# MCH_FPGA_Banks_66_68_HP_FMC.net
KiCad netlist of a schematic drawn in Altium Designer
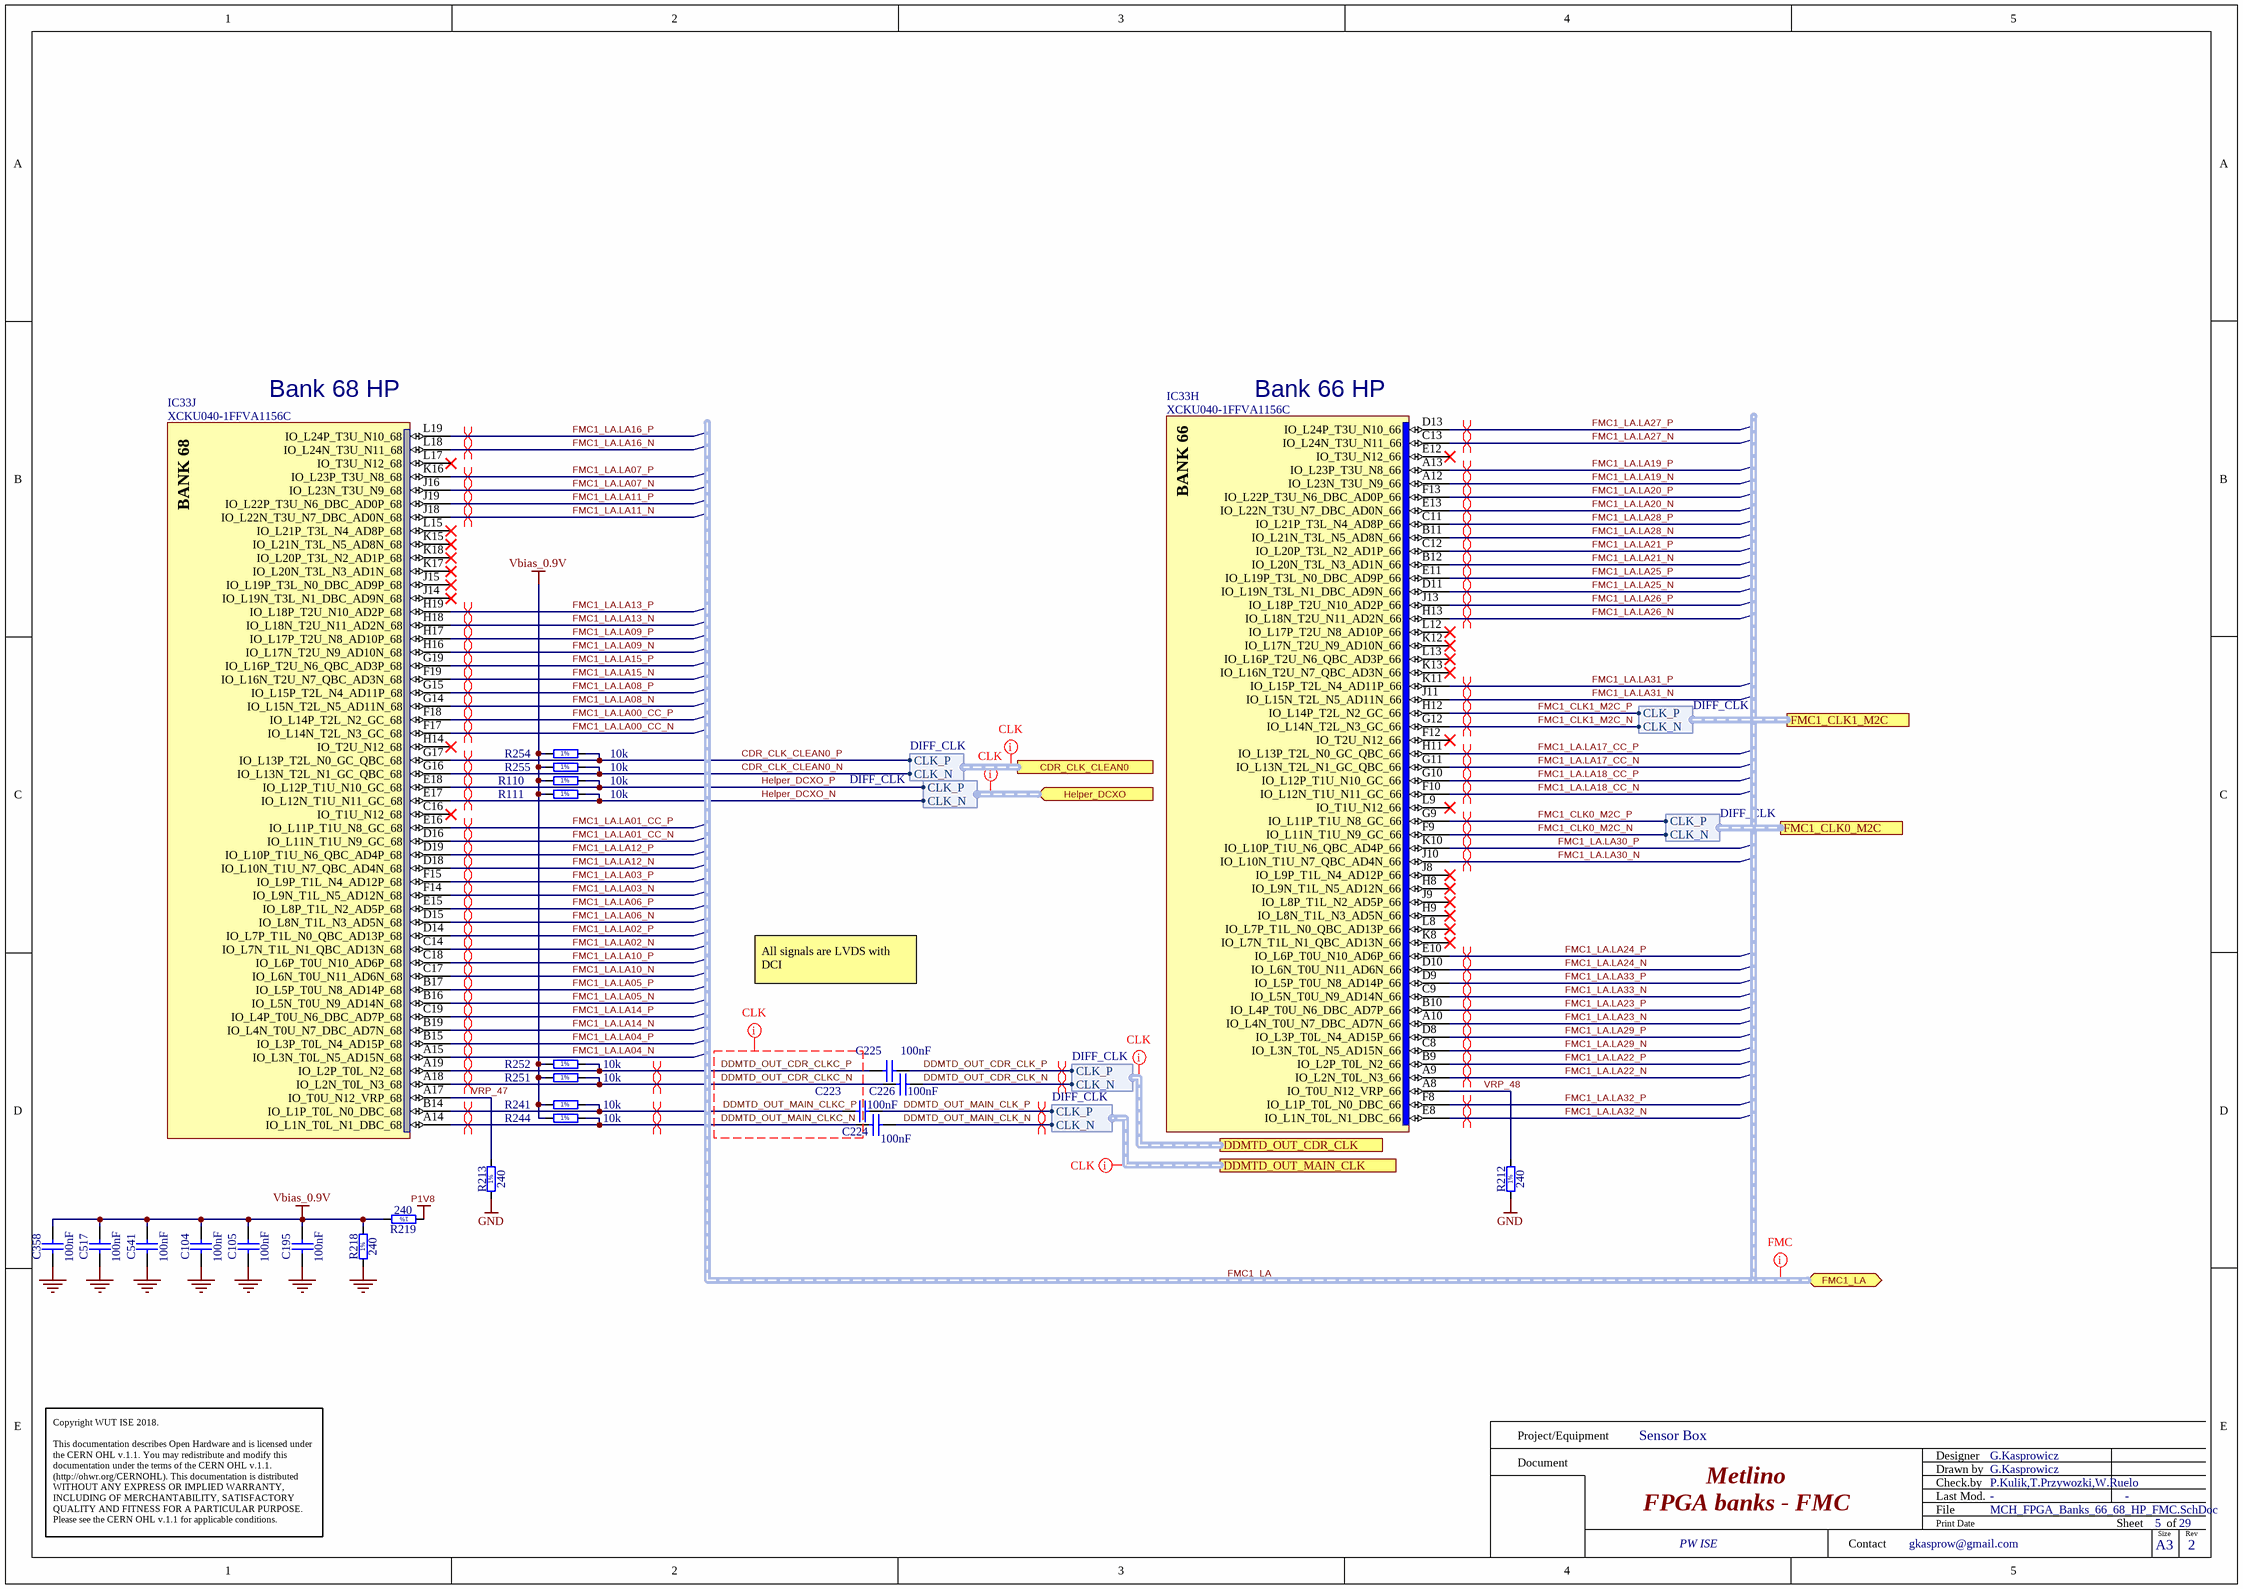
[diagram p0: MCH_FPGA_Banks_66_68_HP_FMC.SchDoc]

(export (version "E")
  (design (tool "Eeschema 10.0.6"))
  (components
    (comp (ref "C104")
      (value "100nF")
      (footprint "CAPC0603X33N")
      (description "Non-polarised capacitor")
      (fields
        (field (name "MANUFACTURER PART NUMBER") "CC0201_100NF_6.3V_10%_X5R")
        (field (name "MANUFACTURER") "GENERIC")
        (field (name "AUTHOR") "CERN DEM JLC")
      )
      (libsource (lib "Capacitors") (part "Capacitor - non polarized"))
    )
    (comp (ref "C105")
      (value "100nF")
      (footprint "CAPC0603X33N")
      (description "Non-polarised capacitor")
      (fields
        (field (name "MANUFACTURER PART NUMBER") "CC0201_100NF_6.3V_10%_X5R")
        (field (name "MANUFACTURER") "GENERIC")
        (field (name "AUTHOR") "CERN DEM JLC")
      )
      (libsource (lib "Capacitors") (part "Capacitor - non polarized"))
    )
    (comp (ref "C195")
      (value "100nF")
      (footprint "CAPC0603X33N")
      (description "Non-polarised capacitor")
      (fields
        (field (name "MANUFACTURER PART NUMBER") "CC0201_100NF_6.3V_10%_X5R")
        (field (name "MANUFACTURER") "GENERIC")
        (field (name "AUTHOR") "CERN DEM JLC")
      )
      (libsource (lib "Capacitors") (part "Capacitor - non polarized"))
    )
    (comp (ref "C223")
      (value "100nF")
      (footprint "CAPC0603X33N")
      (description "Non-polarised capacitor")
      (fields
        (field (name "MANUFACTURER PART NUMBER") "CC0201_100NF_6.3V_10%_X5R")
        (field (name "MANUFACTURER") "GENERIC")
        (field (name "AUTHOR") "CERN DEM JLC")
      )
      (libsource (lib "Capacitors") (part "Capacitor - non polarized"))
    )
    (comp (ref "C224")
      (value "100nF")
      (footprint "CAPC0603X33N")
      (description "Non-polarised capacitor")
      (fields
        (field (name "MANUFACTURER PART NUMBER") "CC0201_100NF_6.3V_10%_X5R")
        (field (name "MANUFACTURER") "GENERIC")
        (field (name "AUTHOR") "CERN DEM JLC")
      )
      (libsource (lib "Capacitors") (part "Capacitor - non polarized"))
    )
    (comp (ref "C225")
      (value "100nF")
      (footprint "CAPC0603X33N")
      (description "Non-polarised capacitor")
      (fields
        (field (name "MANUFACTURER PART NUMBER") "CC0201_100NF_6.3V_10%_X5R")
        (field (name "MANUFACTURER") "GENERIC")
        (field (name "AUTHOR") "CERN DEM JLC")
      )
      (libsource (lib "Capacitors") (part "Capacitor - non polarized"))
    )
    (comp (ref "C226")
      (value "100nF")
      (footprint "CAPC0603X33N")
      (description "Non-polarised capacitor")
      (fields
        (field (name "MANUFACTURER PART NUMBER") "CC0201_100NF_6.3V_10%_X5R")
        (field (name "MANUFACTURER") "GENERIC")
        (field (name "AUTHOR") "CERN DEM JLC")
      )
      (libsource (lib "Capacitors") (part "Capacitor - non polarized"))
    )
    (comp (ref "C358")
      (value "100nF")
      (footprint "CAPC0603X33N")
      (description "Non-polarised capacitor")
      (fields
        (field (name "MANUFACTURER PART NUMBER") "CC0201_100NF_6.3V_10%_X5R")
        (field (name "MANUFACTURER") "GENERIC")
        (field (name "AUTHOR") "CERN DEM JLC")
      )
      (libsource (lib "Capacitors") (part "Capacitor - non polarized"))
    )
    (comp (ref "C517")
      (value "100nF")
      (footprint "CAPC0603X33N")
      (description "Non-polarised capacitor")
      (fields
        (field (name "MANUFACTURER PART NUMBER") "CC0201_100NF_6.3V_10%_X5R")
        (field (name "MANUFACTURER") "GENERIC")
        (field (name "AUTHOR") "CERN DEM JLC")
      )
      (libsource (lib "Capacitors") (part "Capacitor - non polarized"))
    )
    (comp (ref "C541")
      (value "100nF")
      (footprint "CAPC0603X33N")
      (description "Non-polarised capacitor")
      (fields
        (field (name "MANUFACTURER PART NUMBER") "CC0201_100NF_6.3V_10%_X5R")
        (field (name "MANUFACTURER") "GENERIC")
        (field (name "AUTHOR") "CERN DEM JLC")
      )
      (libsource (lib "Capacitors") (part "Capacitor - non polarized"))
    )
    (comp (ref "IC33")
      (value "XCKU040-1FFVA1156C")
      (footprint "BGA1156C100P34X34_3500X3500X350")
      (description "Kintex UltraScale FPGA, 520 I/O, 530K Cells, 1156-Ball BGA, Speed Grade 1, Commercial Grade")
      (fields (field (name "MANUFACTURER") "XILINX") (field (name "AUTHOR") "CERN DEM CA"))
      (libsource (lib "ICs And Semiconductors") (part "XCKU040-1FFVA1156C"))
    )
    (comp (ref "R110")
      (value "10k")
      (footprint "RESC1005X40N")
      (description "Resistor - 1%")
      (fields
        (field (name "MANUFACTURER PART NUMBER") "R0402_10K_1%_0.0625W_100PPM")
        (field (name "MANUFACTURER") "GENERIC")
        (field (name "AUTHOR") "CERN DEM JLC")
      )
      (libsource (lib "Resistors") (part "Resistor - 1%"))
    )
    (comp (ref "R111")
      (value "10k")
      (footprint "RESC1005X40N")
      (description "Resistor - 1%")
      (fields
        (field (name "MANUFACTURER PART NUMBER") "R0402_10K_1%_0.0625W_100PPM")
        (field (name "MANUFACTURER") "GENERIC")
        (field (name "AUTHOR") "CERN DEM JLC")
      )
      (libsource (lib "Resistors") (part "Resistor - 1%"))
    )
    (comp (ref "R212")
      (value "240")
      (footprint "RESC1005X40N")
      (description "Resistor - 1%")
      (fields
        (field (name "MANUFACTURER PART NUMBER") "R0402_240R_1%_0.0625W_100PPM")
        (field (name "MANUFACTURER") "GENERIC")
        (field (name "AUTHOR") "CERN DEM JLC")
      )
      (libsource (lib "Resistors") (part "Resistor - 1%"))
    )
    (comp (ref "R213")
      (value "240")
      (footprint "RESC1005X40N")
      (description "Resistor - 1%")
      (fields
        (field (name "MANUFACTURER PART NUMBER") "R0402_240R_1%_0.0625W_100PPM")
        (field (name "MANUFACTURER") "GENERIC")
        (field (name "AUTHOR") "CERN DEM JLC")
      )
      (libsource (lib "Resistors") (part "Resistor - 1%"))
    )
    (comp (ref "R218")
      (value "240")
      (footprint "RESC1005X40N")
      (description "Resistor - 1%")
      (fields
        (field (name "MANUFACTURER PART NUMBER") "R0402_240R_1%_0.0625W_100PPM")
        (field (name "MANUFACTURER") "GENERIC")
        (field (name "AUTHOR") "CERN DEM JLC")
      )
      (libsource (lib "Resistors") (part "Resistor - 1%"))
    )
    (comp (ref "R219")
      (value "240")
      (footprint "RESC1005X40N")
      (description "Resistor - 1%")
      (fields
        (field (name "MANUFACTURER PART NUMBER") "R0402_240R_1%_0.0625W_100PPM")
        (field (name "MANUFACTURER") "GENERIC")
        (field (name "AUTHOR") "CERN DEM JLC")
      )
      (libsource (lib "Resistors") (part "Resistor - 1%"))
    )
    (comp (ref "R241")
      (value "10k")
      (footprint "RESC1005X40N")
      (description "Resistor - 1%")
      (fields
        (field (name "MANUFACTURER PART NUMBER") "R0402_10K_1%_0.0625W_100PPM")
        (field (name "MANUFACTURER") "GENERIC")
        (field (name "AUTHOR") "CERN DEM JLC")
      )
      (libsource (lib "Resistors") (part "Resistor - 1%"))
    )
    (comp (ref "R244")
      (value "10k")
      (footprint "RESC1005X40N")
      (description "Resistor - 1%")
      (fields
        (field (name "MANUFACTURER PART NUMBER") "R0402_10K_1%_0.0625W_100PPM")
        (field (name "MANUFACTURER") "GENERIC")
        (field (name "AUTHOR") "CERN DEM JLC")
      )
      (libsource (lib "Resistors") (part "Resistor - 1%"))
    )
    (comp (ref "R251")
      (value "10k")
      (footprint "RESC1005X40N")
      (description "Resistor - 1%")
      (fields
        (field (name "MANUFACTURER PART NUMBER") "R0402_10K_1%_0.0625W_100PPM")
        (field (name "MANUFACTURER") "GENERIC")
        (field (name "AUTHOR") "CERN DEM JLC")
      )
      (libsource (lib "Resistors") (part "Resistor - 1%"))
    )
    (comp (ref "R252")
      (value "10k")
      (footprint "RESC1005X40N")
      (description "Resistor - 1%")
      (fields
        (field (name "MANUFACTURER PART NUMBER") "R0402_10K_1%_0.0625W_100PPM")
        (field (name "MANUFACTURER") "GENERIC")
        (field (name "AUTHOR") "CERN DEM JLC")
      )
      (libsource (lib "Resistors") (part "Resistor - 1%"))
    )
    (comp (ref "R254")
      (value "10k")
      (footprint "RESC1005X40N")
      (description "Resistor - 1%")
      (fields
        (field (name "MANUFACTURER PART NUMBER") "R0402_10K_1%_0.0625W_100PPM")
        (field (name "MANUFACTURER") "GENERIC")
        (field (name "AUTHOR") "CERN DEM JLC")
      )
      (libsource (lib "Resistors") (part "Resistor - 1%"))
    )
    (comp (ref "R255")
      (value "10k")
      (footprint "RESC1005X40N")
      (description "Resistor - 1%")
      (fields
        (field (name "MANUFACTURER PART NUMBER") "R0402_10K_1%_0.0625W_100PPM")
        (field (name "MANUFACTURER") "GENERIC")
        (field (name "AUTHOR") "CERN DEM JLC")
      )
      (libsource (lib "Resistors") (part "Resistor - 1%"))
    )
  )
  (nets
    (net (code "3") (name "/CDR_CLK_CLEAN0_N") (class "Default")
      (node (ref "IC33") (pin "G16") (pinfunction "IO_L13N_T2L_N1_GC_QBC_68_G16") (pintype "bidirectional"))
      (node (ref "R255") (pin "2") (pinfunction "2_2") (pintype "passive"))
    )
    (net (code "4") (name "/CDR_CLK_CLEAN0_P") (class "Default")
      (node (ref "IC33") (pin "G17") (pinfunction "IO_L13P_T2L_N0_GC_QBC_68_G17") (pintype "bidirectional"))
      (node (ref "R254") (pin "2") (pinfunction "2_2") (pintype "passive"))
    )
    (net (code "5") (name "/DDMTD_OUT_CDR_CLKC_N") (class "Default")
      (node (ref "C226") (pin "1") (pinfunction "1_1") (pintype "passive"))
      (node (ref "IC33") (pin "A18") (pinfunction "IO_L2N_T0L_N3_68_A18") (pintype "bidirectional"))
      (node (ref "R251") (pin "2") (pinfunction "2_2") (pintype "passive"))
    )
    (net (code "6") (name "/DDMTD_OUT_CDR_CLKC_P") (class "Default")
      (node (ref "C225") (pin "1") (pinfunction "1_1") (pintype "passive"))
      (node (ref "IC33") (pin "A19") (pinfunction "IO_L2P_T0L_N2_68_A19") (pintype "bidirectional"))
      (node (ref "R252") (pin "2") (pinfunction "2_2") (pintype "passive"))
    )
    (net (code "7") (name "/DDMTD_OUT_CDR_CLK_N") (class "Default")
      (node (ref "C226") (pin "2") (pinfunction "2_2") (pintype "passive"))
    )
    (net (code "8") (name "/DDMTD_OUT_CDR_CLK_P") (class "Default")
      (node (ref "C225") (pin "2") (pinfunction "2_2") (pintype "passive"))
    )
    (net (code "9") (name "/DDMTD_OUT_MAIN_CLKC_N") (class "Default")
      (node (ref "C224") (pin "1") (pinfunction "1_1") (pintype "passive"))
      (node (ref "IC33") (pin "A14") (pinfunction "IO_L1N_T0L_N1_DBC_68_A14") (pintype "bidirectional"))
      (node (ref "R244") (pin "2") (pinfunction "2_2") (pintype "passive"))
    )
    (net (code "10") (name "/DDMTD_OUT_MAIN_CLKC_P") (class "Default")
      (node (ref "C223") (pin "1") (pinfunction "1_1") (pintype "passive"))
      (node (ref "IC33") (pin "B14") (pinfunction "IO_L1P_T0L_N0_DBC_68_B14") (pintype "bidirectional"))
      (node (ref "R241") (pin "2") (pinfunction "2_2") (pintype "passive"))
    )
    (net (code "11") (name "/DDMTD_OUT_MAIN_CLK_N") (class "Default")
      (node (ref "C224") (pin "2") (pinfunction "2_2") (pintype "passive"))
    )
    (net (code "12") (name "/DDMTD_OUT_MAIN_CLK_P") (class "Default")
      (node (ref "C223") (pin "2") (pinfunction "2_2") (pintype "passive"))
    )
    (net (code "13") (name "/FMC1_CLK0_M2C_N") (class "Default")
      (node (ref "IC33") (pin "F9") (pinfunction "IO_L11N_T1U_N9_GC_66_F9") (pintype "bidirectional"))
    )
    (net (code "14") (name "/FMC1_CLK0_M2C_P") (class "Default")
      (node (ref "IC33") (pin "G9") (pinfunction "IO_L11P_T1U_N8_GC_66_G9") (pintype "bidirectional"))
    )
    (net (code "15") (name "/FMC1_CLK1_M2C_N") (class "Default")
      (node (ref "IC33") (pin "G12") (pinfunction "IO_L14N_T2L_N3_GC_66_G12") (pintype "bidirectional"))
    )
    (net (code "16") (name "/FMC1_CLK1_M2C_P") (class "Default")
      (node (ref "IC33") (pin "H12") (pinfunction "IO_L14P_T2L_N2_GC_66_H12") (pintype "bidirectional"))
    )
    (net (code "17") (name "/FMC1_LA.LA00_CC_N") (class "Default")
      (node (ref "IC33") (pin "F17") (pinfunction "IO_L14N_T2L_N3_GC_68_F17") (pintype "bidirectional"))
    )
    (net (code "18") (name "/FMC1_LA.LA00_CC_P") (class "Default")
      (node (ref "IC33") (pin "F18") (pinfunction "IO_L14P_T2L_N2_GC_68_F18") (pintype "bidirectional"))
    )
    (net (code "19") (name "/FMC1_LA.LA01_CC_N") (class "Default")
      (node (ref "IC33") (pin "D16") (pinfunction "IO_L11N_T1U_N9_GC_68_D16") (pintype "bidirectional"))
    )
    (net (code "20") (name "/FMC1_LA.LA01_CC_P") (class "Default")
      (node (ref "IC33") (pin "E16") (pinfunction "IO_L11P_T1U_N8_GC_68_E16") (pintype "bidirectional"))
    )
    (net (code "21") (name "/FMC1_LA.LA02_N") (class "Default")
      (node (ref "IC33") (pin "C14") (pinfunction "IO_L7N_T1L_N1_QBC_AD13N_68_C14") (pintype "bidirectional"))
    )
    (net (code "22") (name "/FMC1_LA.LA02_P") (class "Default")
      (node (ref "IC33") (pin "D14") (pinfunction "IO_L7P_T1L_N0_QBC_AD13P_68_D14") (pintype "bidirectional"))
    )
    (net (code "23") (name "/FMC1_LA.LA03_N") (class "Default")
      (node (ref "IC33") (pin "F14") (pinfunction "IO_L9N_T1L_N5_AD12N_68_F14") (pintype "bidirectional"))
    )
    (net (code "24") (name "/FMC1_LA.LA03_P") (class "Default")
      (node (ref "IC33") (pin "F15") (pinfunction "IO_L9P_T1L_N4_AD12P_68_F15") (pintype "bidirectional"))
    )
    (net (code "25") (name "/FMC1_LA.LA04_N") (class "Default")
      (node (ref "IC33") (pin "A15") (pinfunction "IO_L3N_T0L_N5_AD15N_68_A15") (pintype "bidirectional"))
    )
    (net (code "26") (name "/FMC1_LA.LA04_P") (class "Default")
      (node (ref "IC33") (pin "B15") (pinfunction "IO_L3P_T0L_N4_AD15P_68_B15") (pintype "bidirectional"))
    )
    (net (code "27") (name "/FMC1_LA.LA05_N") (class "Default")
      (node (ref "IC33") (pin "B16") (pinfunction "IO_L5N_T0U_N9_AD14N_68_B16") (pintype "bidirectional"))
    )
    (net (code "28") (name "/FMC1_LA.LA05_P") (class "Default")
      (node (ref "IC33") (pin "B17") (pinfunction "IO_L5P_T0U_N8_AD14P_68_B17") (pintype "bidirectional"))
    )
    (net (code "29") (name "/FMC1_LA.LA06_N") (class "Default")
      (node (ref "IC33") (pin "D15") (pinfunction "IO_L8N_T1L_N3_AD5N_68_D15") (pintype "bidirectional"))
    )
    (net (code "30") (name "/FMC1_LA.LA06_P") (class "Default")
      (node (ref "IC33") (pin "E15") (pinfunction "IO_L8P_T1L_N2_AD5P_68_E15") (pintype "bidirectional"))
    )
    (net (code "31") (name "/FMC1_LA.LA07_N") (class "Default")
      (node (ref "IC33") (pin "J16") (pinfunction "IO_L23N_T3U_N9_68_J16") (pintype "bidirectional"))
    )
    (net (code "32") (name "/FMC1_LA.LA07_P") (class "Default")
      (node (ref "IC33") (pin "K16") (pinfunction "IO_L23P_T3U_N8_68_K16") (pintype "bidirectional"))
    )
    (net (code "33") (name "/FMC1_LA.LA08_N") (class "Default")
      (node (ref "IC33") (pin "G14") (pinfunction "IO_L15N_T2L_N5_AD11N_68_G14") (pintype "bidirectional"))
    )
    (net (code "34") (name "/FMC1_LA.LA08_P") (class "Default")
      (node (ref "IC33") (pin "G15") (pinfunction "IO_L15P_T2L_N4_AD11P_68_G15") (pintype "bidirectional"))
    )
    (net (code "35") (name "/FMC1_LA.LA09_N") (class "Default")
      (node (ref "IC33") (pin "H16") (pinfunction "IO_L17N_T2U_N9_AD10N_68_H16") (pintype "bidirectional"))
    )
    (net (code "36") (name "/FMC1_LA.LA09_P") (class "Default")
      (node (ref "IC33") (pin "H17") (pinfunction "IO_L17P_T2U_N8_AD10P_68_H17") (pintype "bidirectional"))
    )
    (net (code "37") (name "/FMC1_LA.LA10_N") (class "Default")
      (node (ref "IC33") (pin "C17") (pinfunction "IO_L6N_T0U_N11_AD6N_68_C17") (pintype "bidirectional"))
    )
    (net (code "38") (name "/FMC1_LA.LA10_P") (class "Default")
      (node (ref "IC33") (pin "C18") (pinfunction "IO_L6P_T0U_N10_AD6P_68_C18") (pintype "bidirectional"))
    )
    (net (code "39") (name "/FMC1_LA.LA11_N") (class "Default")
      (node (ref "IC33") (pin "J18") (pinfunction "IO_L22N_T3U_N7_DBC_AD0N_68_J18") (pintype "bidirectional"))
    )
    (net (code "40") (name "/FMC1_LA.LA11_P") (class "Default")
      (node (ref "IC33") (pin "J19") (pinfunction "IO_L22P_T3U_N6_DBC_AD0P_68_J19") (pintype "bidirectional"))
    )
    (net (code "41") (name "/FMC1_LA.LA12_N") (class "Default")
      (node (ref "IC33") (pin "D18") (pinfunction "IO_L10N_T1U_N7_QBC_AD4N_68_D18") (pintype "bidirectional"))
    )
    (net (code "42") (name "/FMC1_LA.LA12_P") (class "Default")
      (node (ref "IC33") (pin "D19") (pinfunction "IO_L10P_T1U_N6_QBC_AD4P_68_D19") (pintype "bidirectional"))
    )
    (net (code "43") (name "/FMC1_LA.LA13_N") (class "Default")
      (node (ref "IC33") (pin "H18") (pinfunction "IO_L18N_T2U_N11_AD2N_68_H18") (pintype "bidirectional"))
    )
    (net (code "44") (name "/FMC1_LA.LA13_P") (class "Default")
      (node (ref "IC33") (pin "H19") (pinfunction "IO_L18P_T2U_N10_AD2P_68_H19") (pintype "bidirectional"))
    )
    (net (code "45") (name "/FMC1_LA.LA14_N") (class "Default")
      (node (ref "IC33") (pin "B19") (pinfunction "IO_L4N_T0U_N7_DBC_AD7N_68_B19") (pintype "bidirectional"))
    )
    (net (code "46") (name "/FMC1_LA.LA14_P") (class "Default")
      (node (ref "IC33") (pin "C19") (pinfunction "IO_L4P_T0U_N6_DBC_AD7P_68_C19") (pintype "bidirectional"))
    )
    (net (code "47") (name "/FMC1_LA.LA15_N") (class "Default")
      (node (ref "IC33") (pin "F19") (pinfunction "IO_L16N_T2U_N7_QBC_AD3N_68_F19") (pintype "bidirectional"))
    )
    (net (code "48") (name "/FMC1_LA.LA15_P") (class "Default")
      (node (ref "IC33") (pin "G19") (pinfunction "IO_L16P_T2U_N6_QBC_AD3P_68_G19") (pintype "bidirectional"))
    )
    (net (code "49") (name "/FMC1_LA.LA16_N") (class "Default")
      (node (ref "IC33") (pin "L18") (pinfunction "IO_L24N_T3U_N11_68_L18") (pintype "bidirectional"))
    )
    (net (code "50") (name "/FMC1_LA.LA16_P") (class "Default")
      (node (ref "IC33") (pin "L19") (pinfunction "IO_L24P_T3U_N10_68_L19") (pintype "bidirectional"))
    )
    (net (code "51") (name "/FMC1_LA.LA17_CC_N") (class "Default")
      (node (ref "IC33") (pin "G11") (pinfunction "IO_L13N_T2L_N1_GC_QBC_66_G11") (pintype "bidirectional"))
    )
    (net (code "52") (name "/FMC1_LA.LA17_CC_P") (class "Default")
      (node (ref "IC33") (pin "H11") (pinfunction "IO_L13P_T2L_N0_GC_QBC_66_H11") (pintype "bidirectional"))
    )
    (net (code "53") (name "/FMC1_LA.LA18_CC_N") (class "Default")
      (node (ref "IC33") (pin "F10") (pinfunction "IO_L12N_T1U_N11_GC_66_F10") (pintype "bidirectional"))
    )
    (net (code "54") (name "/FMC1_LA.LA18_CC_P") (class "Default")
      (node (ref "IC33") (pin "G10") (pinfunction "IO_L12P_T1U_N10_GC_66_G10") (pintype "bidirectional"))
    )
    (net (code "55") (name "/FMC1_LA.LA19_N") (class "Default")
      (node (ref "IC33") (pin "A12") (pinfunction "IO_L23N_T3U_N9_66_A12") (pintype "bidirectional"))
    )
    (net (code "56") (name "/FMC1_LA.LA19_P") (class "Default")
      (node (ref "IC33") (pin "A13") (pinfunction "IO_L23P_T3U_N8_66_A13") (pintype "bidirectional"))
    )
    (net (code "57") (name "/FMC1_LA.LA20_N") (class "Default")
      (node (ref "IC33") (pin "E13") (pinfunction "IO_L22N_T3U_N7_DBC_AD0N_66_E13") (pintype "bidirectional"))
    )
    (net (code "58") (name "/FMC1_LA.LA20_P") (class "Default")
      (node (ref "IC33") (pin "F13") (pinfunction "IO_L22P_T3U_N6_DBC_AD0P_66_F13") (pintype "bidirectional"))
    )
    (net (code "59") (name "/FMC1_LA.LA21_N") (class "Default")
      (node (ref "IC33") (pin "B12") (pinfunction "IO_L20N_T3L_N3_AD1N_66_B12") (pintype "bidirectional"))
    )
    (net (code "60") (name "/FMC1_LA.LA21_P") (class "Default")
      (node (ref "IC33") (pin "C12") (pinfunction "IO_L20P_T3L_N2_AD1P_66_C12") (pintype "bidirectional"))
    )
    (net (code "61") (name "/FMC1_LA.LA22_N") (class "Default")
      (node (ref "IC33") (pin "A9") (pinfunction "IO_L2N_T0L_N3_66_A9") (pintype "bidirectional"))
    )
    (net (code "62") (name "/FMC1_LA.LA22_P") (class "Default")
      (node (ref "IC33") (pin "B9") (pinfunction "IO_L2P_T0L_N2_66_B9") (pintype "bidirectional"))
    )
    (net (code "63") (name "/FMC1_LA.LA23_N") (class "Default")
      (node (ref "IC33") (pin "A10") (pinfunction "IO_L4N_T0U_N7_DBC_AD7N_66_A10") (pintype "bidirectional"))
    )
    (net (code "64") (name "/FMC1_LA.LA23_P") (class "Default")
      (node (ref "IC33") (pin "B10") (pinfunction "IO_L4P_T0U_N6_DBC_AD7P_66_B10") (pintype "bidirectional"))
    )
    (net (code "65") (name "/FMC1_LA.LA24_N") (class "Default")
      (node (ref "IC33") (pin "D10") (pinfunction "IO_L6N_T0U_N11_AD6N_66_D10") (pintype "bidirectional"))
    )
    (net (code "66") (name "/FMC1_LA.LA24_P") (class "Default")
      (node (ref "IC33") (pin "E10") (pinfunction "IO_L6P_T0U_N10_AD6P_66_E10") (pintype "bidirectional"))
    )
    (net (code "67") (name "/FMC1_LA.LA25_N") (class "Default")
      (node (ref "IC33") (pin "D11") (pinfunction "IO_L19N_T3L_N1_DBC_AD9N_66_D11") (pintype "bidirectional"))
    )
    (net (code "68") (name "/FMC1_LA.LA25_P") (class "Default")
      (node (ref "IC33") (pin "E11") (pinfunction "IO_L19P_T3L_N0_DBC_AD9P_66_E11") (pintype "bidirectional"))
    )
    (net (code "69") (name "/FMC1_LA.LA26_N") (class "Default")
      (node (ref "IC33") (pin "H13") (pinfunction "IO_L18N_T2U_N11_AD2N_66_H13") (pintype "bidirectional"))
    )
    (net (code "70") (name "/FMC1_LA.LA26_P") (class "Default")
      (node (ref "IC33") (pin "J13") (pinfunction "IO_L18P_T2U_N10_AD2P_66_J13") (pintype "bidirectional"))
    )
    (net (code "71") (name "/FMC1_LA.LA27_N") (class "Default")
      (node (ref "IC33") (pin "C13") (pinfunction "IO_L24N_T3U_N11_66_C13") (pintype "bidirectional"))
    )
    (net (code "72") (name "/FMC1_LA.LA27_P") (class "Default")
      (node (ref "IC33") (pin "D13") (pinfunction "IO_L24P_T3U_N10_66_D13") (pintype "bidirectional"))
    )
    (net (code "73") (name "/FMC1_LA.LA28_N") (class "Default")
      (node (ref "IC33") (pin "B11") (pinfunction "IO_L21N_T3L_N5_AD8N_66_B11") (pintype "bidirectional"))
    )
    (net (code "74") (name "/FMC1_LA.LA28_P") (class "Default")
      (node (ref "IC33") (pin "C11") (pinfunction "IO_L21P_T3L_N4_AD8P_66_C11") (pintype "bidirectional"))
    )
    (net (code "75") (name "/FMC1_LA.LA29_N") (class "Default")
      (node (ref "IC33") (pin "C8") (pinfunction "IO_L3N_T0L_N5_AD15N_66_C8") (pintype "bidirectional"))
    )
    (net (code "76") (name "/FMC1_LA.LA29_P") (class "Default")
      (node (ref "IC33") (pin "D8") (pinfunction "IO_L3P_T0L_N4_AD15P_66_D8") (pintype "bidirectional"))
    )
    (net (code "77") (name "/FMC1_LA.LA30_N") (class "Default")
      (node (ref "IC33") (pin "J10") (pinfunction "IO_L10N_T1U_N7_QBC_AD4N_66_J10") (pintype "bidirectional"))
    )
    (net (code "78") (name "/FMC1_LA.LA30_P") (class "Default")
      (node (ref "IC33") (pin "K10") (pinfunction "IO_L10P_T1U_N6_QBC_AD4P_66_K10") (pintype "bidirectional"))
    )
    (net (code "79") (name "/FMC1_LA.LA31_N") (class "Default")
      (node (ref "IC33") (pin "J11") (pinfunction "IO_L15N_T2L_N5_AD11N_66_J11") (pintype "bidirectional"))
    )
    (net (code "80") (name "/FMC1_LA.LA31_P") (class "Default")
      (node (ref "IC33") (pin "K11") (pinfunction "IO_L15P_T2L_N4_AD11P_66_K11") (pintype "bidirectional"))
    )
    (net (code "81") (name "/FMC1_LA.LA32_N") (class "Default")
      (node (ref "IC33") (pin "E8") (pinfunction "IO_L1N_T0L_N1_DBC_66_E8") (pintype "bidirectional"))
    )
    (net (code "82") (name "/FMC1_LA.LA32_P") (class "Default")
      (node (ref "IC33") (pin "F8") (pinfunction "IO_L1P_T0L_N0_DBC_66_F8") (pintype "bidirectional"))
    )
    (net (code "83") (name "/FMC1_LA.LA33_N") (class "Default")
      (node (ref "IC33") (pin "C9") (pinfunction "IO_L5N_T0U_N9_AD14N_66_C9") (pintype "bidirectional"))
    )
    (net (code "84") (name "/FMC1_LA.LA33_P") (class "Default")
      (node (ref "IC33") (pin "D9") (pinfunction "IO_L5P_T0U_N8_AD14P_66_D9") (pintype "bidirectional"))
    )
    (net (code "85") (name "/Helper_DCXO_N") (class "Default")
      (node (ref "IC33") (pin "E17") (pinfunction "IO_L12N_T1U_N11_GC_68_E17") (pintype "bidirectional"))
      (node (ref "R111") (pin "2") (pinfunction "2_2") (pintype "passive"))
    )
    (net (code "86") (name "/Helper_DCXO_P") (class "Default")
      (node (ref "IC33") (pin "E18") (pinfunction "IO_L12P_T1U_N10_GC_68_E18") (pintype "bidirectional"))
      (node (ref "R110") (pin "2") (pinfunction "2_2") (pintype "passive"))
    )
    (net (code "87") (name "/VRP_47") (class "Default")
      (node (ref "IC33") (pin "A17") (pinfunction "IO_T0U_N12_VRP_68_A17") (pintype "bidirectional"))
      (node (ref "R213") (pin "2") (pinfunction "2_2") (pintype "passive"))
    )
    (net (code "88") (name "/VRP_48") (class "Default")
      (node (ref "IC33") (pin "A8") (pinfunction "IO_T0U_N12_VRP_66_A8") (pintype "bidirectional"))
      (node (ref "R212") (pin "2") (pinfunction "2_2") (pintype "passive"))
    )
    (net (code "91") (name "GND") (class "Default")
      (node (ref "C104") (pin "2") (pinfunction "2_2") (pintype "passive"))
      (node (ref "C105") (pin "2") (pinfunction "2_2") (pintype "passive"))
      (node (ref "C195") (pin "2") (pinfunction "2_2") (pintype "passive"))
      (node (ref "C358") (pin "2") (pinfunction "2_2") (pintype "passive"))
      (node (ref "C517") (pin "2") (pinfunction "2_2") (pintype "passive"))
      (node (ref "C541") (pin "2") (pinfunction "2_2") (pintype "passive"))
      (node (ref "R212") (pin "1") (pinfunction "1_1") (pintype "passive"))
      (node (ref "R213") (pin "1") (pinfunction "1_1") (pintype "passive"))
      (node (ref "R218") (pin "1") (pinfunction "1_1") (pintype "passive"))
    )
    (net (code "92") (name "P1V8") (class "Default")
      (node (ref "R219") (pin "1") (pinfunction "1_1") (pintype "passive"))
    )
    (net (code "93") (name "Vbias_0.9V") (class "Default")
      (node (ref "C104") (pin "1") (pinfunction "1_1") (pintype "passive"))
      (node (ref "C105") (pin "1") (pinfunction "1_1") (pintype "passive"))
      (node (ref "C195") (pin "1") (pinfunction "1_1") (pintype "passive"))
      (node (ref "C358") (pin "1") (pinfunction "1_1") (pintype "passive"))
      (node (ref "C517") (pin "1") (pinfunction "1_1") (pintype "passive"))
      (node (ref "C541") (pin "1") (pinfunction "1_1") (pintype "passive"))
      (node (ref "R110") (pin "1") (pinfunction "1_1") (pintype "passive"))
      (node (ref "R111") (pin "1") (pinfunction "1_1") (pintype "passive"))
      (node (ref "R218") (pin "2") (pinfunction "2_2") (pintype "passive"))
      (node (ref "R219") (pin "2") (pinfunction "2_2") (pintype "passive"))
      (node (ref "R241") (pin "1") (pinfunction "1_1") (pintype "passive"))
      (node (ref "R244") (pin "1") (pinfunction "1_1") (pintype "passive"))
      (node (ref "R251") (pin "1") (pinfunction "1_1") (pintype "passive"))
      (node (ref "R252") (pin "1") (pinfunction "1_1") (pintype "passive"))
      (node (ref "R254") (pin "1") (pinfunction "1_1") (pintype "passive"))
      (node (ref "R255") (pin "1") (pinfunction "1_1") (pintype "passive"))
    )
    (net (code "94") (name "unconnected-(IC33H-IO_L7N_T1L_N1_QBC_AD13N_66-PadK8)") (class "Default")
      (node (ref "IC33") (pin "K8") (pinfunction "IO_L7N_T1L_N1_QBC_AD13N_66_K8") (pintype "bidirectional+no_connect"))
    )
    (net (code "95") (name "unconnected-(IC33H-IO_L7P_T1L_N0_QBC_AD13P_66-PadL8)") (class "Default")
      (node (ref "IC33") (pin "L8") (pinfunction "IO_L7P_T1L_N0_QBC_AD13P_66_L8") (pintype "bidirectional+no_connect"))
    )
    (net (code "96") (name "unconnected-(IC33H-IO_L8N_T1L_N3_AD5N_66-PadH9)") (class "Default")
      (node (ref "IC33") (pin "H9") (pinfunction "IO_L8N_T1L_N3_AD5N_66_H9") (pintype "bidirectional+no_connect"))
    )
    (net (code "97") (name "unconnected-(IC33H-IO_L8P_T1L_N2_AD5P_66-PadJ9)") (class "Default")
      (node (ref "IC33") (pin "J9") (pinfunction "IO_L8P_T1L_N2_AD5P_66_J9") (pintype "bidirectional+no_connect"))
    )
    (net (code "98") (name "unconnected-(IC33H-IO_L9N_T1L_N5_AD12N_66-PadH8)") (class "Default")
      (node (ref "IC33") (pin "H8") (pinfunction "IO_L9N_T1L_N5_AD12N_66_H8") (pintype "bidirectional+no_connect"))
    )
    (net (code "99") (name "unconnected-(IC33H-IO_L9P_T1L_N4_AD12P_66-PadJ8)") (class "Default")
      (node (ref "IC33") (pin "J8") (pinfunction "IO_L9P_T1L_N4_AD12P_66_J8") (pintype "bidirectional+no_connect"))
    )
    (net (code "100") (name "unconnected-(IC33H-IO_L16N_T2U_N7_QBC_AD3N_66-PadK13)") (class "Default")
      (node (ref "IC33") (pin "K13") (pinfunction "IO_L16N_T2U_N7_QBC_AD3N_66_K13") (pintype "bidirectional+no_connect"))
    )
    (net (code "101") (name "unconnected-(IC33H-IO_L16P_T2U_N6_QBC_AD3P_66-PadL13)") (class "Default")
      (node (ref "IC33") (pin "L13") (pinfunction "IO_L16P_T2U_N6_QBC_AD3P_66_L13") (pintype "bidirectional+no_connect"))
    )
    (net (code "102") (name "unconnected-(IC33H-IO_L17N_T2U_N9_AD10N_66-PadK12)") (class "Default")
      (node (ref "IC33") (pin "K12") (pinfunction "IO_L17N_T2U_N9_AD10N_66_K12") (pintype "bidirectional+no_connect"))
    )
    (net (code "103") (name "unconnected-(IC33H-IO_L17P_T2U_N8_AD10P_66-PadL12)") (class "Default")
      (node (ref "IC33") (pin "L12") (pinfunction "IO_L17P_T2U_N8_AD10P_66_L12") (pintype "bidirectional+no_connect"))
    )
    (net (code "104") (name "unconnected-(IC33H-IO_T1U_N12_66-PadL9)") (class "Default")
      (node (ref "IC33") (pin "L9") (pinfunction "IO_T1U_N12_66_L9") (pintype "bidirectional+no_connect"))
    )
    (net (code "105") (name "unconnected-(IC33H-IO_T2U_N12_66-PadF12)") (class "Default")
      (node (ref "IC33") (pin "F12") (pinfunction "IO_T2U_N12_66_F12") (pintype "bidirectional+no_connect"))
    )
    (net (code "106") (name "unconnected-(IC33H-IO_T3U_N12_66-PadE12)") (class "Default")
      (node (ref "IC33") (pin "E12") (pinfunction "IO_T3U_N12_66_E12") (pintype "bidirectional+no_connect"))
    )
    (net (code "107") (name "unconnected-(IC33J-IO_L19N_T3L_N1_DBC_AD9N_68-PadJ14)") (class "Default")
      (node (ref "IC33") (pin "J14") (pinfunction "IO_L19N_T3L_N1_DBC_AD9N_68_J14") (pintype "bidirectional+no_connect"))
    )
    (net (code "108") (name "unconnected-(IC33J-IO_L19P_T3L_N0_DBC_AD9P_68-PadJ15)") (class "Default")
      (node (ref "IC33") (pin "J15") (pinfunction "IO_L19P_T3L_N0_DBC_AD9P_68_J15") (pintype "bidirectional+no_connect"))
    )
    (net (code "109") (name "unconnected-(IC33J-IO_L20N_T3L_N3_AD1N_68-PadK17)") (class "Default")
      (node (ref "IC33") (pin "K17") (pinfunction "IO_L20N_T3L_N3_AD1N_68_K17") (pintype "bidirectional+no_connect"))
    )
    (net (code "110") (name "unconnected-(IC33J-IO_L20P_T3L_N2_AD1P_68-PadK18)") (class "Default")
      (node (ref "IC33") (pin "K18") (pinfunction "IO_L20P_T3L_N2_AD1P_68_K18") (pintype "bidirectional+no_connect"))
    )
    (net (code "111") (name "unconnected-(IC33J-IO_L21N_T3L_N5_AD8N_68-PadK15)") (class "Default")
      (node (ref "IC33") (pin "K15") (pinfunction "IO_L21N_T3L_N5_AD8N_68_K15") (pintype "bidirectional+no_connect"))
    )
    (net (code "112") (name "unconnected-(IC33J-IO_L21P_T3L_N4_AD8P_68-PadL15)") (class "Default")
      (node (ref "IC33") (pin "L15") (pinfunction "IO_L21P_T3L_N4_AD8P_68_L15") (pintype "bidirectional+no_connect"))
    )
    (net (code "113") (name "unconnected-(IC33J-IO_T1U_N12_68-PadC16)") (class "Default")
      (node (ref "IC33") (pin "C16") (pinfunction "IO_T1U_N12_68_C16") (pintype "bidirectional+no_connect"))
    )
    (net (code "114") (name "unconnected-(IC33J-IO_T2U_N12_68-PadH14)") (class "Default")
      (node (ref "IC33") (pin "H14") (pinfunction "IO_T2U_N12_68_H14") (pintype "bidirectional+no_connect"))
    )
    (net (code "115") (name "unconnected-(IC33J-IO_T3U_N12_68-PadL17)") (class "Default")
      (node (ref "IC33") (pin "L17") (pinfunction "IO_T3U_N12_68_L17") (pintype "bidirectional+no_connect"))
    )
  )
)
